# Interfaces.net
KiCad netlist of a schematic drawn in Altium Designer
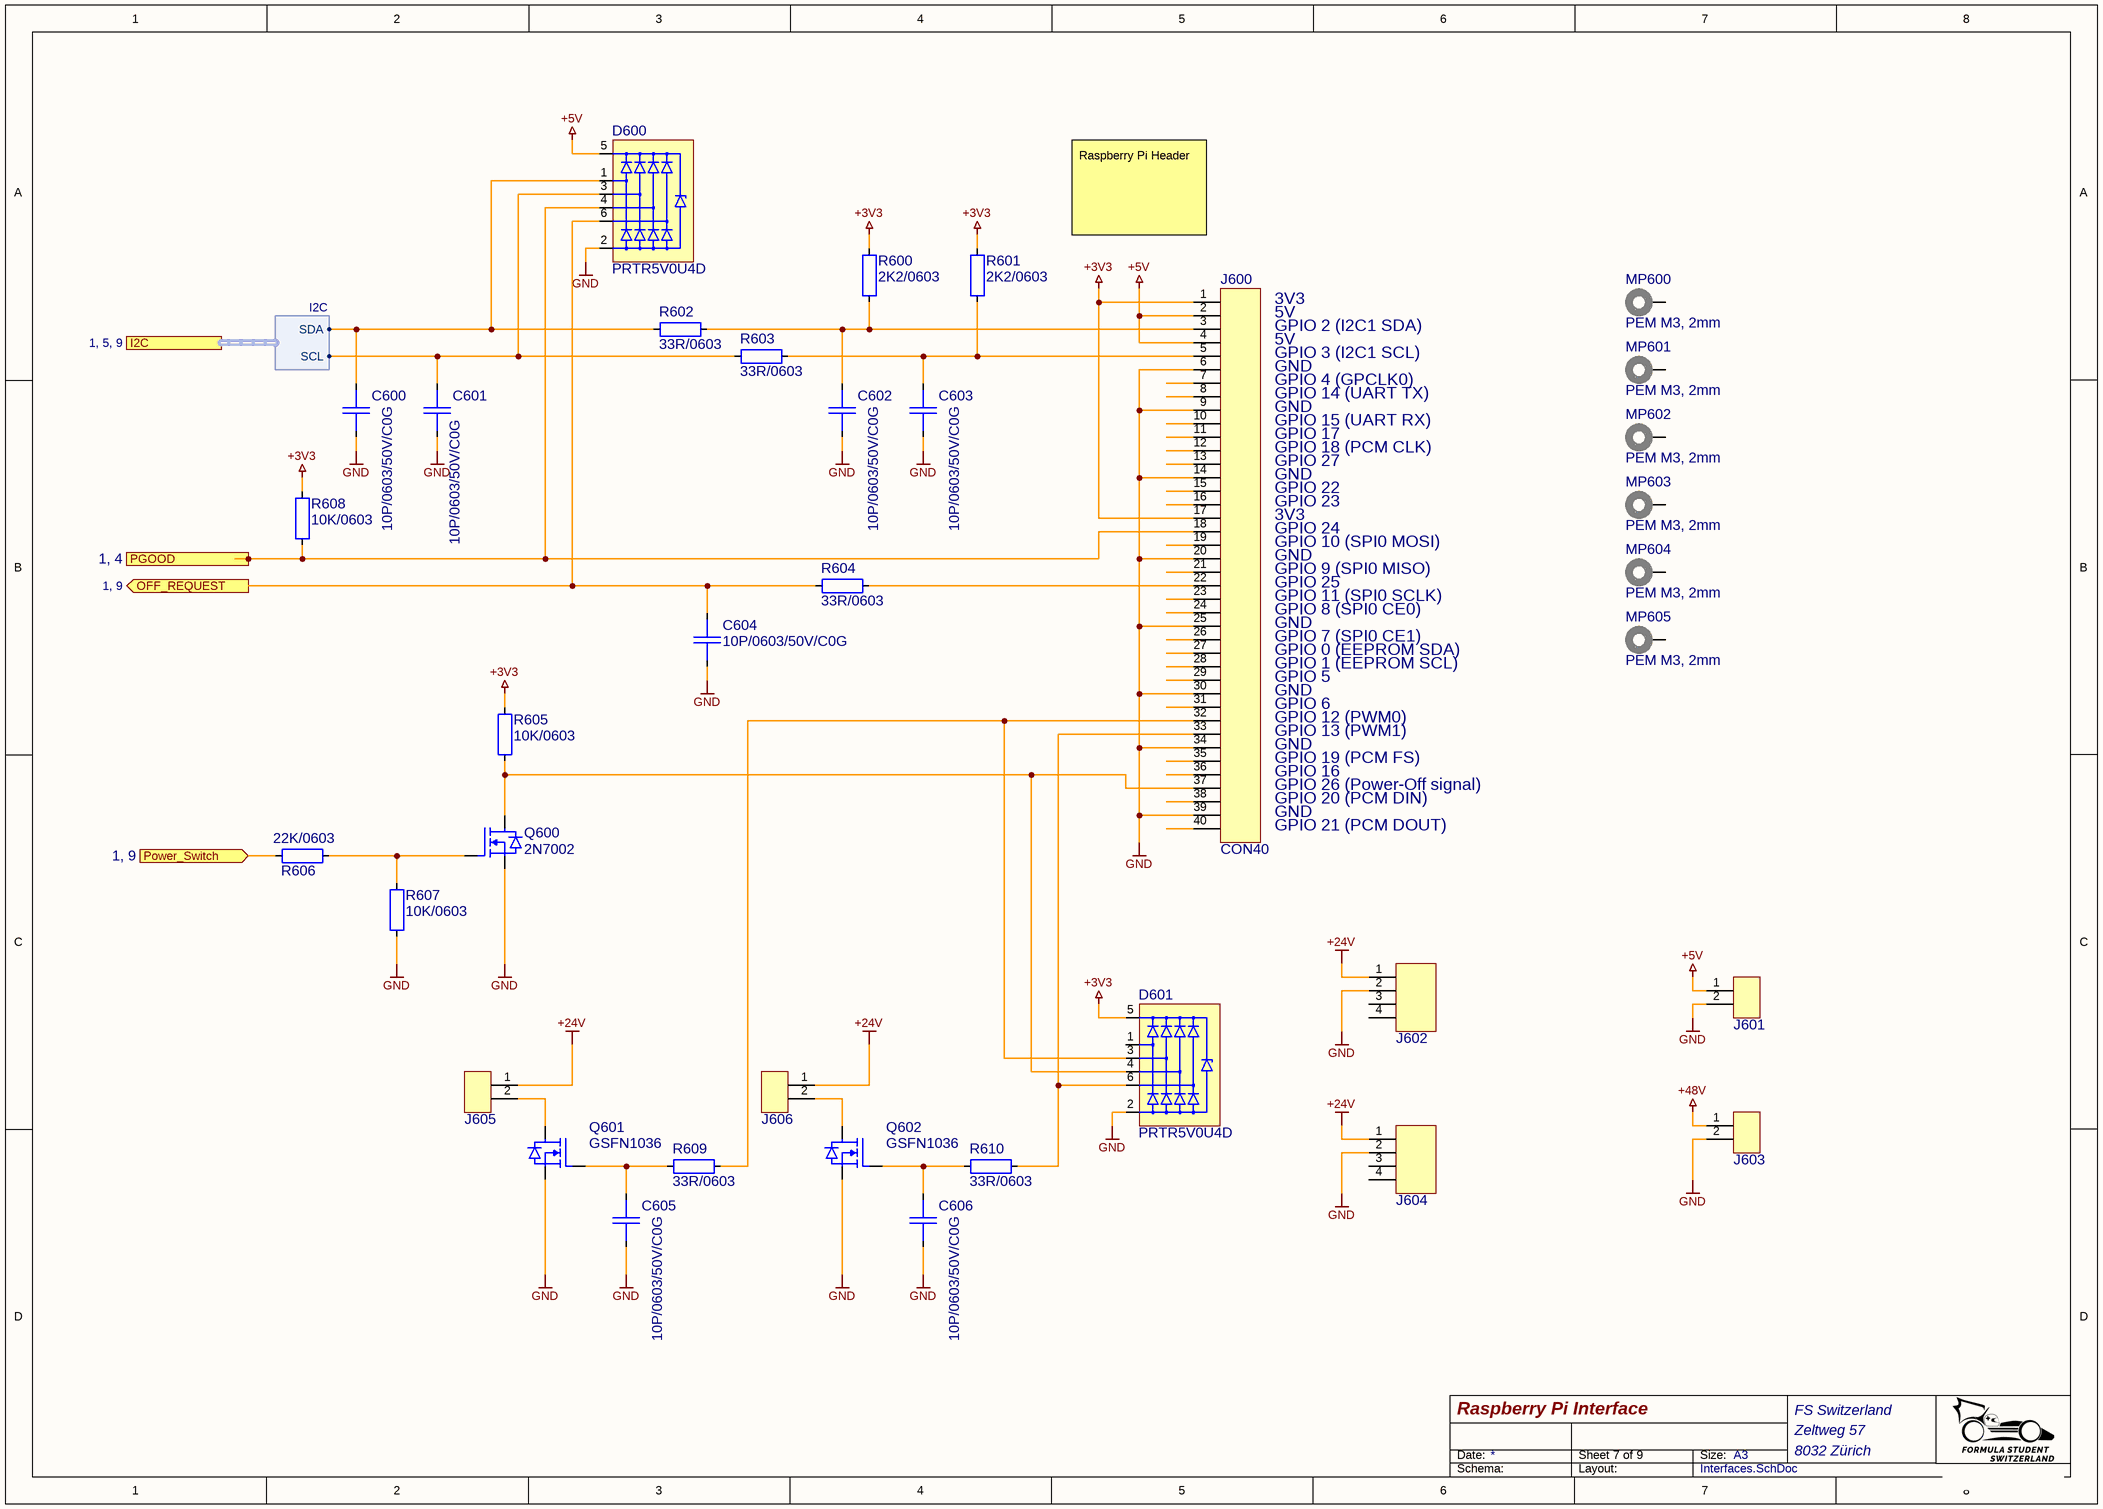
[diagram p0: Interfaces.SchDoc]

(export (version "E")
  (design (tool "Eeschema 10.0.6"))
  (components
    (comp (ref "C600")
      (value "10P/0603/50V/C0G")
      (footprint "CAP0603_C0G")
      (description "CAP SM 0603 10pF 50V C0G")
      (fields (field (name "MANUFACTURER") "GENERIC"))
      (libsource (lib "daniw_altium_lib") (part "C"))
    )
    (comp (ref "C601")
      (value "10P/0603/50V/C0G")
      (footprint "CAP0603_C0G")
      (description "CAP SM 0603 10pF 50V C0G")
      (fields (field (name "MANUFACTURER") "GENERIC"))
      (libsource (lib "daniw_altium_lib") (part "C"))
    )
    (comp (ref "C602")
      (value "10P/0603/50V/C0G")
      (footprint "CAP0603_C0G")
      (description "CAP SM 0603 10pF 50V C0G")
      (fields (field (name "MANUFACTURER") "GENERIC"))
      (libsource (lib "daniw_altium_lib") (part "C"))
    )
    (comp (ref "C603")
      (value "10P/0603/50V/C0G")
      (footprint "CAP0603_C0G")
      (description "CAP SM 0603 10pF 50V C0G")
      (fields (field (name "MANUFACTURER") "GENERIC"))
      (libsource (lib "daniw_altium_lib") (part "C"))
    )
    (comp (ref "C604")
      (value "10P/0603/50V/C0G")
      (footprint "CAP0603_C0G")
      (description "CAP SM 0603 10pF 50V C0G")
      (fields (field (name "MANUFACTURER") "GENERIC"))
      (libsource (lib "daniw_altium_lib") (part "C"))
    )
    (comp (ref "C605")
      (value "10P/0603/50V/C0G")
      (footprint "CAP0603_C0G")
      (description "CAP SM 0603 10pF 50V C0G")
      (fields (field (name "MANUFACTURER") "GENERIC"))
      (libsource (lib "daniw_altium_lib") (part "C"))
    )
    (comp (ref "C606")
      (value "10P/0603/50V/C0G")
      (footprint "CAP0603_C0G")
      (description "CAP SM 0603 10pF 50V C0G")
      (fields (field (name "MANUFACTURER") "GENERIC"))
      (libsource (lib "daniw_altium_lib") (part "C"))
    )
    (comp (ref "D600")
      (value "PRTR5V0U4D")
      (footprint "SOT2395P280X125-6-NW")
      (description "quadruple rail-to-rail ESD protection 5V")
      (fields (field (name "MANUFACTURER") "Nexperia"))
      (libsource (lib "daniw_altium_lib") (part "D_ESD_QUAD"))
    )
    (comp (ref "D601")
      (value "PRTR5V0U4D")
      (footprint "SOT2395P280X125-6-NW")
      (description "quadruple rail-to-rail ESD protection 5V")
      (fields (field (name "MANUFACTURER") "Nexperia"))
      (libsource (lib "daniw_altium_lib") (part "D_ESD_QUAD"))
    )
    (comp (ref "J600")
      (value "CON40")
      (footprint "HEAD_254_2X20_Tray")
      (description "Header 100 mil")
      (fields (field (name "PART NUMBER") "Header_2x20_Tray") (field (name "MANUFACTURER") "GENERIC"))
      (libsource (lib "daniw_altium_lib") (part "CON40"))
    )
    (comp (ref "J601")
      (value "5600200220")
      (footprint "5600200220")
      (description "DuraClik Wire-to-Board Header, Single Row, Vertical, 2 Circuits, Tin (Sn) Over Nickel, Natural")
      (fields (field (name "PART NUMBER") "DuraClick_1x2_VERT_SMD") (field (name "MANUFACTURER") "Molex"))
      (libsource (lib "") (part "CON2_1"))
    )
    (comp (ref "J602")
      (value "430450412")
      (footprint "430450412")
      (fields (field (name "PART NUMBER") "Microfit_3.0_2x2_VERT_THT"))
      (libsource (lib "daniw_altium_lib") (part "CON4"))
    )
    (comp (ref "J603")
      (value "430450212")
      (footprint "430450212")
      (fields (field (name "PART NUMBER") "Microfit_3.0_1x2_VERT_THT"))
      (libsource (lib "") (part "CON2_1"))
    )
    (comp (ref "J604")
      (value "430450412")
      (footprint "430450412")
      (fields (field (name "PART NUMBER") "Microfit_3.0_2x2_VERT_THT"))
      (libsource (lib "daniw_altium_lib") (part "CON4"))
    )
    (comp (ref "J605")
      (value "5600200220")
      (footprint "5600200220")
      (description "DuraClik Wire-to-Board Header, Single Row, Vertical, 2 Circuits, Tin (Sn) Over Nickel, Natural")
      (fields (field (name "PART NUMBER") "DuraClick_1x2_VERT_SMD") (field (name "MANUFACTURER") "Molex"))
      (libsource (lib "daniw_altium_lib") (part "CON2"))
    )
    (comp (ref "J606")
      (value "5600200220")
      (footprint "5600200220")
      (description "DuraClik Wire-to-Board Header, Single Row, Vertical, 2 Circuits, Tin (Sn) Over Nickel, Natural")
      (fields (field (name "PART NUMBER") "DuraClick_1x2_VERT_SMD") (field (name "MANUFACTURER") "Molex"))
      (libsource (lib "daniw_altium_lib") (part "CON2"))
    )
    (comp (ref "MP600")
      (value "PEM M3, 2mm")
      (footprint "MECH_SMTSO3020CTJ")
      (description "Solder Nut M3x0.5, 2mm")
      (fields (field (name "MANUFACTURER") "GENERIC"))
      (libsource (lib "daniw_altium_lib") (part "Nut"))
    )
    (comp (ref "MP601")
      (value "PEM M3, 2mm")
      (footprint "MECH_SMTSO3020CTJ")
      (description "Solder Nut M3x0.5, 2mm")
      (fields (field (name "MANUFACTURER") "GENERIC"))
      (libsource (lib "daniw_altium_lib") (part "Nut"))
    )
    (comp (ref "MP602")
      (value "PEM M3, 2mm")
      (footprint "MECH_SMTSO3020CTJ")
      (description "Solder Nut M3x0.5, 2mm")
      (fields (field (name "MANUFACTURER") "GENERIC"))
      (libsource (lib "daniw_altium_lib") (part "Nut"))
    )
    (comp (ref "MP603")
      (value "PEM M3, 2mm")
      (footprint "MECH_SMTSO3020CTJ")
      (description "Solder Nut M3x0.5, 2mm")
      (fields (field (name "MANUFACTURER") "GENERIC"))
      (libsource (lib "daniw_altium_lib") (part "Nut"))
    )
    (comp (ref "MP604")
      (value "PEM M3, 2mm")
      (footprint "MECH_SMTSO3020CTJ")
      (description "Solder Nut M3x0.5, 2mm")
      (fields (field (name "MANUFACTURER") "GENERIC"))
      (libsource (lib "daniw_altium_lib") (part "Nut"))
    )
    (comp (ref "MP605")
      (value "PEM M3, 2mm")
      (footprint "MECH_SMTSO3020CTJ")
      (description "Solder Nut M3x0.5, 2mm")
      (fields (field (name "MANUFACTURER") "GENERIC"))
      (libsource (lib "daniw_altium_lib") (part "Nut"))
    )
    (comp (ref "Q600")
      (value "2N7002")
      (footprint "SOT2395P280X125-3-SE")
      (description "60V 115mA 1.2Ω@10V,500mA 200mW 2.1V@250uA N Channel SOT-23 MOSFETs")
      (fields (field (name "MANUFACTURER") "GENERIC"))
      (libsource (lib "daniw_altium_lib") (part "MOSFET N_SOT23"))
    )
    (comp (ref "Q601")
      (value "GSFN1036")
      (footprint "SON065P330X330X075-5-TH245X175")
      (description "N-Kanal 100 V 35 A (Tc) 52W (Tc) Oberflächenmontage 8-PPAK (3,1x3,05)")
      (fields (field (name "MANUFACTURER") "Good-Ark Semiconductor"))
      (libsource (lib "daniw_altium_lib") (part "MOSFET N"))
    )
    (comp (ref "Q602")
      (value "GSFN1036")
      (footprint "SON065P330X330X075-5-TH245X175")
      (description "N-Kanal 100 V 35 A (Tc) 52W (Tc) Oberflächenmontage 8-PPAK (3,1x3,05)")
      (fields (field (name "MANUFACTURER") "Good-Ark Semiconductor"))
      (libsource (lib "daniw_altium_lib") (part "MOSFET N"))
    )
    (comp (ref "R600")
      (value "2K2/0603")
      (footprint "R0603-0.40-WW")
      (description "RES SM 0603 2K2")
      (fields (field (name "MANUFACTURER") "GENERIC"))
      (libsource (lib "daniw_altium_lib") (part "R"))
    )
    (comp (ref "R601")
      (value "2K2/0603")
      (footprint "R0603-0.40-WW")
      (description "RES SM 0603 2K2")
      (fields (field (name "MANUFACTURER") "GENERIC"))
      (libsource (lib "daniw_altium_lib") (part "R"))
    )
    (comp (ref "R602")
      (value "33R/0603")
      (footprint "R0603-0.40-WW")
      (description "RES SM 0603 33R")
      (fields (field (name "MANUFACTURER") "GENERIC"))
      (libsource (lib "daniw_altium_lib") (part "R"))
    )
    (comp (ref "R603")
      (value "33R/0603")
      (footprint "R0603-0.40-WW")
      (description "RES SM 0603 33R")
      (fields (field (name "MANUFACTURER") "GENERIC"))
      (libsource (lib "daniw_altium_lib") (part "R"))
    )
    (comp (ref "R604")
      (value "33R/0603")
      (footprint "R0603-0.40-WW")
      (description "RES SM 0603 33R")
      (fields (field (name "MANUFACTURER") "GENERIC"))
      (libsource (lib "daniw_altium_lib") (part "R"))
    )
    (comp (ref "R605")
      (value "10K/0603")
      (footprint "R0603-0.40-WW")
      (description "RES SM 0603 10K")
      (fields (field (name "MANUFACTURER") "GENERIC"))
      (libsource (lib "daniw_altium_lib") (part "R"))
    )
    (comp (ref "R606")
      (value "22K/0603")
      (footprint "R0603-0.40-WW")
      (description "RES SM 0603 22K")
      (fields (field (name "MANUFACTURER") "GENERIC"))
      (libsource (lib "daniw_altium_lib") (part "R"))
    )
    (comp (ref "R607")
      (value "10K/0603")
      (footprint "R0603-0.40-WW")
      (description "RES SM 0603 10K")
      (fields (field (name "MANUFACTURER") "GENERIC"))
      (libsource (lib "daniw_altium_lib") (part "R"))
    )
    (comp (ref "R608")
      (value "10K/0603")
      (footprint "R0603-0.40-WW")
      (description "RES SM 0603 10K")
      (fields (field (name "MANUFACTURER") "GENERIC"))
      (libsource (lib "daniw_altium_lib") (part "R"))
    )
    (comp (ref "R609")
      (value "33R/0603")
      (footprint "R0603-0.40-WW")
      (description "RES SM 0603 33R")
      (fields (field (name "MANUFACTURER") "GENERIC"))
      (libsource (lib "daniw_altium_lib") (part "R"))
    )
    (comp (ref "R610")
      (value "33R/0603")
      (footprint "R0603-0.40-WW")
      (description "RES SM 0603 33R")
      (fields (field (name "MANUFACTURER") "GENERIC"))
      (libsource (lib "daniw_altium_lib") (part "R"))
    )
  )
  (nets
    (net (code "2") (name "+3V3") (class "Default")
      (node (ref "D601") (pin "5") (pinfunction "5_5") (pintype "passive"))
      (node (ref "J600") (pin "1") (pintype "passive"))
      (node (ref "J600") (pin "17") (pintype "passive"))
      (node (ref "R600") (pin "2") (pinfunction "2_2") (pintype "passive"))
      (node (ref "R601") (pin "2") (pinfunction "2_2") (pintype "passive"))
      (node (ref "R605") (pin "1") (pinfunction "1_1") (pintype "passive"))
      (node (ref "R608") (pin "1") (pinfunction "1_1") (pintype "passive"))
    )
    (net (code "3") (name "+5V") (class "Default")
      (node (ref "D600") (pin "5") (pinfunction "5_5") (pintype "passive"))
      (node (ref "J600") (pin "2") (pintype "passive"))
      (node (ref "J600") (pin "4") (pintype "passive"))
      (node (ref "J601") (pin "1") (pintype "passive"))
    )
    (net (code "4") (name "+24V") (class "Default")
      (node (ref "J602") (pin "1") (pintype "passive"))
      (node (ref "J604") (pin "1") (pintype "passive"))
      (node (ref "J605") (pin "1") (pintype "passive"))
      (node (ref "J606") (pin "1") (pintype "passive"))
    )
    (net (code "5") (name "+48V") (class "Default") (node (ref "J603") (pin "1") (pintype "passive")))
    (net (code "6") (name "/OFF_REQUEST") (class "Default")
      (node (ref "C604") (pin "1") (pinfunction "1_1") (pintype "passive"))
      (node (ref "D600") (pin "6") (pinfunction "6_6") (pintype "passive"))
      (node (ref "R604") (pin "1") (pinfunction "1_1") (pintype "passive"))
    )
    (net (code "7") (name "/PGOOD") (class "Default")
      (node (ref "D600") (pin "4") (pinfunction "4_4") (pintype "passive"))
      (node (ref "J600") (pin "18") (pintype "passive"))
      (node (ref "R608") (pin "2") (pinfunction "2_2") (pintype "passive"))
    )
    (net (code "8") (name "/Power_Switch") (class "Default")
      (node (ref "R606") (pin "1") (pinfunction "1_1") (pintype "passive"))
    )
    (net (code "10") (name "GND") (class "Default")
      (node (ref "C600") (pin "2") (pinfunction "2_2") (pintype "passive"))
      (node (ref "C601") (pin "2") (pinfunction "2_2") (pintype "passive"))
      (node (ref "C602") (pin "2") (pinfunction "2_2") (pintype "passive"))
      (node (ref "C603") (pin "2") (pinfunction "2_2") (pintype "passive"))
      (node (ref "C604") (pin "2") (pinfunction "2_2") (pintype "passive"))
      (node (ref "C605") (pin "2") (pinfunction "2_2") (pintype "passive"))
      (node (ref "C606") (pin "2") (pinfunction "2_2") (pintype "passive"))
      (node (ref "D600") (pin "2") (pinfunction "2_2") (pintype "passive"))
      (node (ref "D601") (pin "2") (pinfunction "2_2") (pintype "passive"))
      (node (ref "J600") (pin "14") (pintype "passive"))
      (node (ref "J600") (pin "20") (pintype "passive"))
      (node (ref "J600") (pin "25") (pintype "passive"))
      (node (ref "J600") (pin "30") (pintype "passive"))
      (node (ref "J600") (pin "34") (pintype "passive"))
      (node (ref "J600") (pin "39") (pintype "passive"))
      (node (ref "J600") (pin "6") (pintype "passive"))
      (node (ref "J600") (pin "9") (pintype "passive"))
      (node (ref "J601") (pin "2") (pintype "passive"))
      (node (ref "J602") (pin "2") (pintype "passive"))
      (node (ref "J603") (pin "2") (pintype "passive"))
      (node (ref "J604") (pin "2") (pintype "passive"))
      (node (ref "Q600") (pin "2") (pinfunction "SOURCE_2") (pintype "passive"))
      (node (ref "Q601") (pin "S") (pinfunction "SOURCE_S") (pintype "passive"))
      (node (ref "Q602") (pin "S") (pinfunction "SOURCE_S") (pintype "passive"))
      (node (ref "R607") (pin "2") (pinfunction "2_2") (pintype "passive"))
    )
    (net (code "11") (name "Net-(C600-Pad1)") (class "Default")
      (node (ref "C600") (pin "1") (pinfunction "1_1") (pintype "passive"))
      (node (ref "D600") (pin "1") (pinfunction "1_1") (pintype "passive"))
      (node (ref "R602") (pin "1") (pinfunction "1_1") (pintype "passive"))
    )
    (net (code "12") (name "Net-(C601-Pad1)") (class "Default")
      (node (ref "C601") (pin "1") (pinfunction "1_1") (pintype "passive"))
      (node (ref "D600") (pin "3") (pinfunction "3_3") (pintype "passive"))
      (node (ref "R603") (pin "1") (pinfunction "1_1") (pintype "passive"))
    )
    (net (code "13") (name "Net-(C602-Pad1)") (class "Default")
      (node (ref "C602") (pin "1") (pinfunction "1_1") (pintype "passive"))
      (node (ref "J600") (pin "3") (pintype "passive"))
      (node (ref "R600") (pin "1") (pinfunction "1_1") (pintype "passive"))
      (node (ref "R602") (pin "2") (pinfunction "2_2") (pintype "passive"))
    )
    (net (code "14") (name "Net-(C603-Pad1)") (class "Default")
      (node (ref "C603") (pin "1") (pinfunction "1_1") (pintype "passive"))
      (node (ref "J600") (pin "5") (pintype "passive"))
      (node (ref "R601") (pin "1") (pinfunction "1_1") (pintype "passive"))
      (node (ref "R603") (pin "2") (pinfunction "2_2") (pintype "passive"))
    )
    (net (code "15") (name "Net-(D601-Pad3)") (class "Default")
      (node (ref "D601") (pin "3") (pinfunction "3_3") (pintype "passive"))
      (node (ref "J600") (pin "32") (pintype "passive"))
      (node (ref "R609") (pin "2") (pinfunction "2_2") (pintype "passive"))
    )
    (net (code "16") (name "Net-(D601-Pad6)") (class "Default")
      (node (ref "D601") (pin "6") (pinfunction "6_6") (pintype "passive"))
      (node (ref "J600") (pin "33") (pintype "passive"))
      (node (ref "R610") (pin "2") (pinfunction "2_2") (pintype "passive"))
    )
    (net (code "17") (name "Net-(J600-Pad22)") (class "Default")
      (node (ref "J600") (pin "22") (pintype "passive"))
      (node (ref "R604") (pin "2") (pinfunction "2_2") (pintype "passive"))
    )
    (net (code "18") (name "Net-(Q600-DRAIN)") (class "Default")
      (node (ref "D601") (pin "4") (pinfunction "4_4") (pintype "passive"))
      (node (ref "J600") (pin "37") (pintype "passive"))
      (node (ref "Q600") (pin "3") (pinfunction "DRAIN_3") (pintype "passive"))
      (node (ref "R605") (pin "2") (pinfunction "2_2") (pintype "passive"))
    )
    (net (code "19") (name "Net-(Q600-GATE)") (class "Default")
      (node (ref "Q600") (pin "1") (pinfunction "GATE_1") (pintype "passive"))
      (node (ref "R606") (pin "2") (pinfunction "2_2") (pintype "passive"))
      (node (ref "R607") (pin "1") (pinfunction "1_1") (pintype "passive"))
    )
    (net (code "20") (name "Net-(Q601-DRAIN)") (class "Default")
      (node (ref "J605") (pin "2") (pintype "passive"))
      (node (ref "Q601") (pin "D") (pinfunction "DRAIN_D") (pintype "passive"))
    )
    (net (code "21") (name "Net-(Q601-GATE)") (class "Default")
      (node (ref "C605") (pin "1") (pinfunction "1_1") (pintype "passive"))
      (node (ref "Q601") (pin "G") (pinfunction "GATE_G") (pintype "passive"))
      (node (ref "R609") (pin "1") (pinfunction "1_1") (pintype "passive"))
    )
    (net (code "22") (name "Net-(Q602-DRAIN)") (class "Default")
      (node (ref "J606") (pin "2") (pintype "passive"))
      (node (ref "Q602") (pin "D") (pinfunction "DRAIN_D") (pintype "passive"))
    )
    (net (code "23") (name "Net-(Q602-GATE)") (class "Default")
      (node (ref "C606") (pin "1") (pinfunction "1_1") (pintype "passive"))
      (node (ref "Q602") (pin "G") (pinfunction "GATE_G") (pintype "passive"))
      (node (ref "R610") (pin "1") (pinfunction "1_1") (pintype "passive"))
    )
    (net (code "24") (name "unconnected-(D601-Pad1)") (class "Default")
      (node (ref "D601") (pin "1") (pinfunction "1_1") (pintype "passive"))
    )
    (net (code "25") (name "unconnected-(J600-Pad7)") (class "Default")
      (node (ref "J600") (pin "7") (pintype "passive"))
    )
    (net (code "26") (name "unconnected-(J600-Pad8)") (class "Default")
      (node (ref "J600") (pin "8") (pintype "passive"))
    )
    (net (code "27") (name "unconnected-(J600-Pad10)") (class "Default")
      (node (ref "J600") (pin "10") (pintype "passive"))
    )
    (net (code "28") (name "unconnected-(J600-Pad11)") (class "Default")
      (node (ref "J600") (pin "11") (pintype "passive"))
    )
    (net (code "29") (name "unconnected-(J600-Pad12)") (class "Default")
      (node (ref "J600") (pin "12") (pintype "passive"))
    )
    (net (code "30") (name "unconnected-(J600-Pad13)") (class "Default")
      (node (ref "J600") (pin "13") (pintype "passive"))
    )
    (net (code "31") (name "unconnected-(J600-Pad15)") (class "Default")
      (node (ref "J600") (pin "15") (pintype "passive"))
    )
    (net (code "32") (name "unconnected-(J600-Pad16)") (class "Default")
      (node (ref "J600") (pin "16") (pintype "passive"))
    )
    (net (code "33") (name "unconnected-(J600-Pad19)") (class "Default")
      (node (ref "J600") (pin "19") (pintype "passive"))
    )
    (net (code "34") (name "unconnected-(J600-Pad21)") (class "Default")
      (node (ref "J600") (pin "21") (pintype "passive"))
    )
    (net (code "35") (name "unconnected-(J600-Pad23)") (class "Default")
      (node (ref "J600") (pin "23") (pintype "passive"))
    )
    (net (code "36") (name "unconnected-(J600-Pad24)") (class "Default")
      (node (ref "J600") (pin "24") (pintype "passive"))
    )
    (net (code "37") (name "unconnected-(J600-Pad26)") (class "Default")
      (node (ref "J600") (pin "26") (pintype "passive"))
    )
    (net (code "38") (name "unconnected-(J600-Pad27)") (class "Default")
      (node (ref "J600") (pin "27") (pintype "passive"))
    )
    (net (code "39") (name "unconnected-(J600-Pad28)") (class "Default")
      (node (ref "J600") (pin "28") (pintype "passive"))
    )
    (net (code "40") (name "unconnected-(J600-Pad29)") (class "Default")
      (node (ref "J600") (pin "29") (pintype "passive"))
    )
    (net (code "41") (name "unconnected-(J600-Pad31)") (class "Default")
      (node (ref "J600") (pin "31") (pintype "passive"))
    )
    (net (code "42") (name "unconnected-(J600-Pad35)") (class "Default")
      (node (ref "J600") (pin "35") (pintype "passive"))
    )
    (net (code "43") (name "unconnected-(J600-Pad36)") (class "Default")
      (node (ref "J600") (pin "36") (pintype "passive"))
    )
    (net (code "44") (name "unconnected-(J600-Pad38)") (class "Default")
      (node (ref "J600") (pin "38") (pintype "passive"))
    )
    (net (code "45") (name "unconnected-(J600-Pad40)") (class "Default")
      (node (ref "J600") (pin "40") (pintype "passive"))
    )
    (net (code "46") (name "unconnected-(J602-Pad3)") (class "Default")
      (node (ref "J602") (pin "3") (pintype "passive"))
    )
    (net (code "47") (name "unconnected-(J602-Pad4)") (class "Default")
      (node (ref "J602") (pin "4") (pintype "passive"))
    )
    (net (code "48") (name "unconnected-(J604-Pad3)") (class "Default")
      (node (ref "J604") (pin "3") (pintype "passive"))
    )
    (net (code "49") (name "unconnected-(J604-Pad4)") (class "Default")
      (node (ref "J604") (pin "4") (pintype "passive"))
    )
    (net (code "50") (name "unconnected-(MP600-Pad1)") (class "Default")
      (node (ref "MP600") (pin "1") (pinfunction "1_1") (pintype "passive"))
    )
    (net (code "51") (name "unconnected-(MP601-Pad1)") (class "Default")
      (node (ref "MP601") (pin "1") (pinfunction "1_1") (pintype "passive"))
    )
    (net (code "52") (name "unconnected-(MP602-Pad1)") (class "Default")
      (node (ref "MP602") (pin "1") (pinfunction "1_1") (pintype "passive"))
    )
    (net (code "53") (name "unconnected-(MP603-Pad1)") (class "Default")
      (node (ref "MP603") (pin "1") (pinfunction "1_1") (pintype "passive"))
    )
    (net (code "54") (name "unconnected-(MP604-Pad1)") (class "Default")
      (node (ref "MP604") (pin "1") (pinfunction "1_1") (pintype "passive"))
    )
    (net (code "55") (name "unconnected-(MP605-Pad1)") (class "Default")
      (node (ref "MP605") (pin "1") (pinfunction "1_1") (pintype "passive"))
    )
  )
)
